# CPU_Board.net
KiCad netlist of a schematic drawn in EAGLE
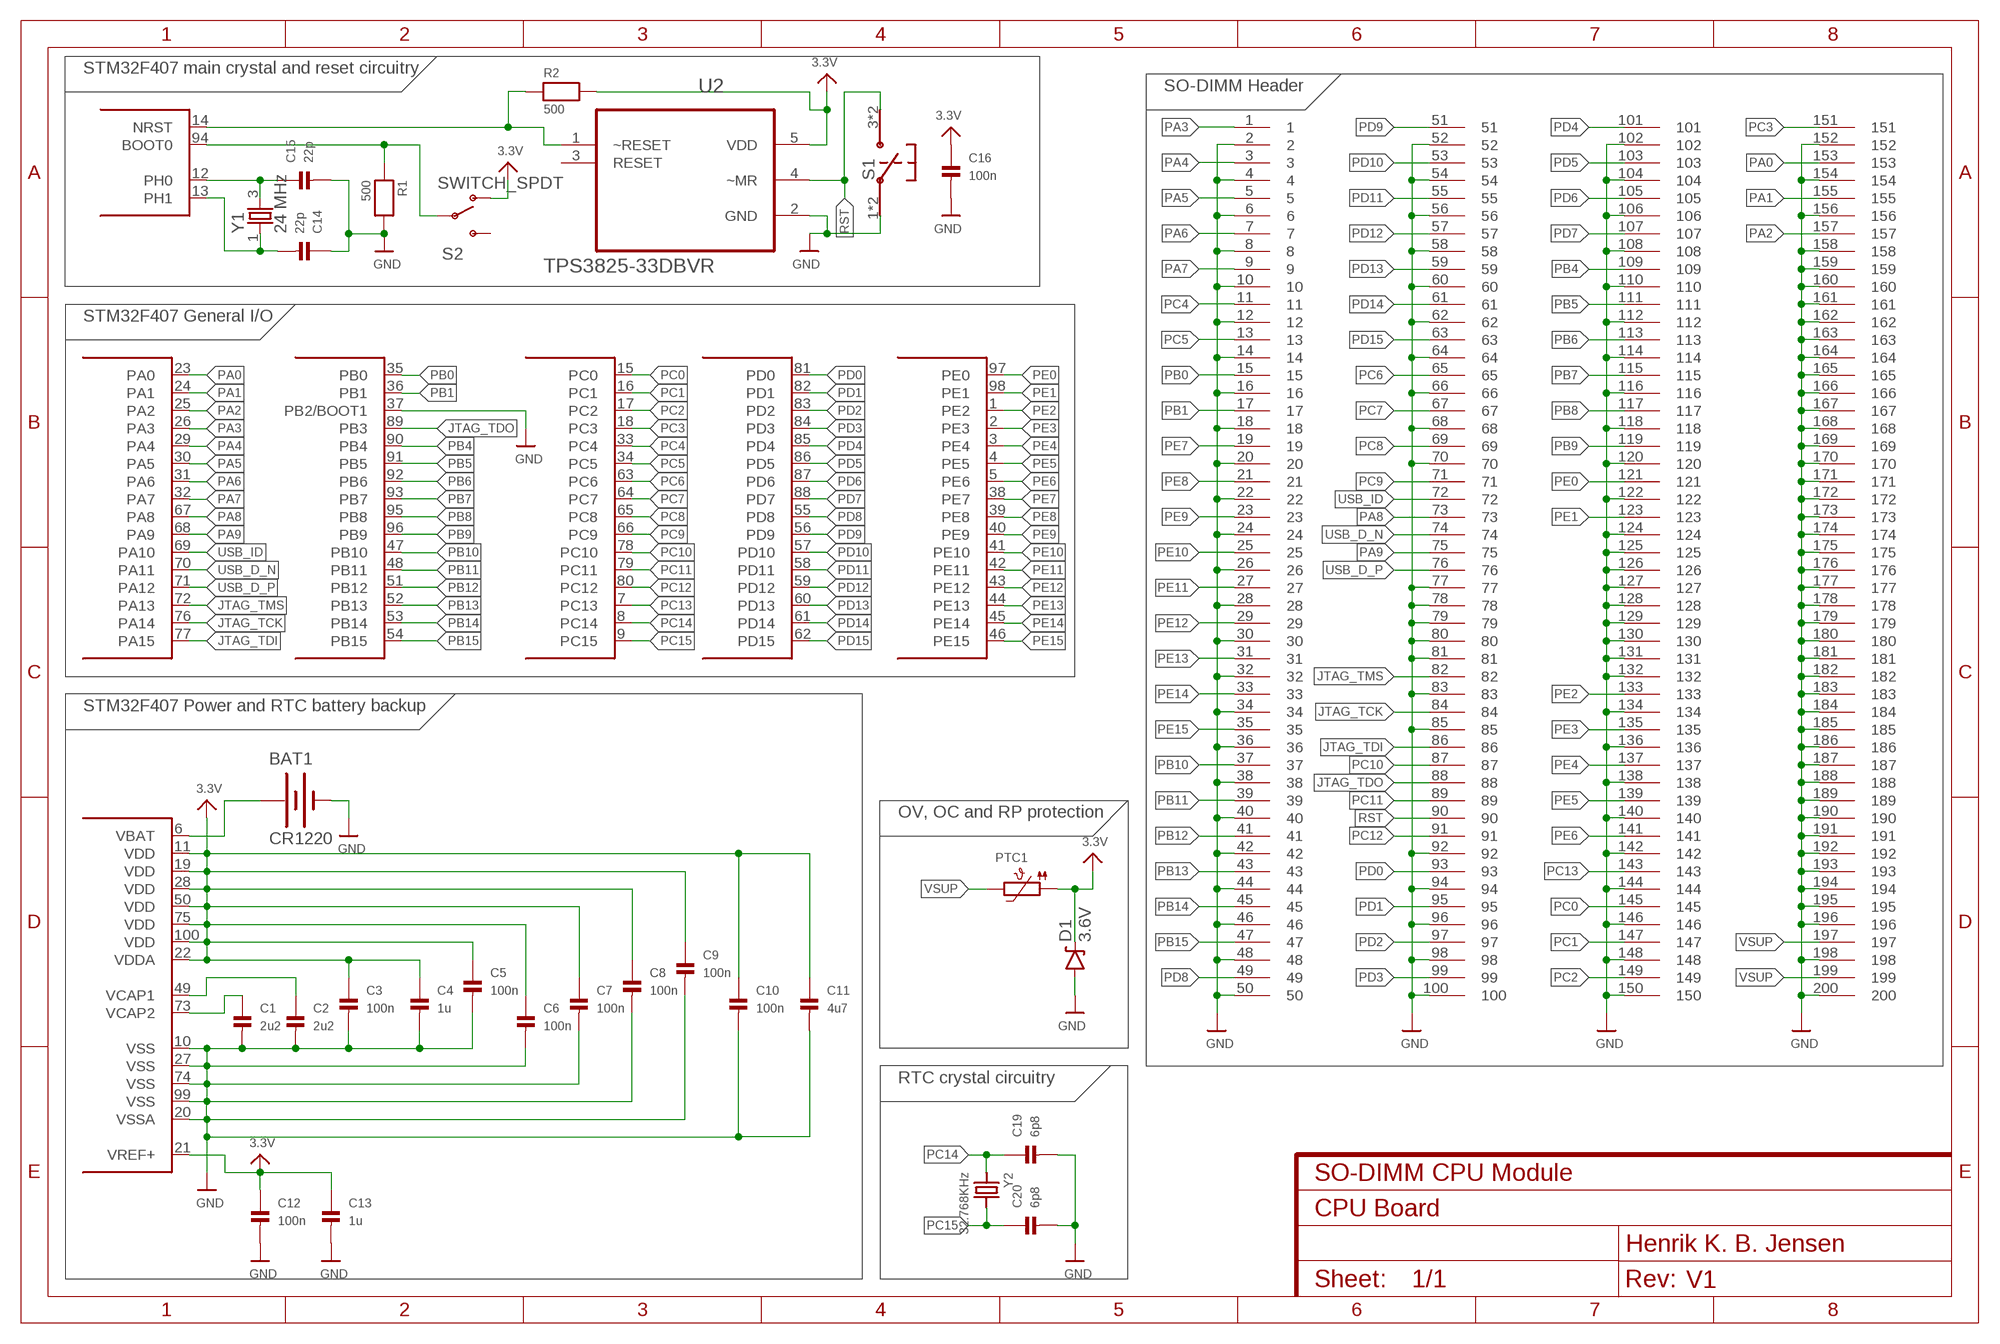
[diagram p0: schematic, sheet 1]

(export (version "E")
  (design (tool "Eeschema 10.0.6"))
  (components
    (comp (ref "BAT1")
      (value "CR1220")
      (footprint "eagle-import:BATTCON_12MM_PTH")
      (libsource (lib "eagle-import") (part "BATTERY12PTH"))
    )
    (comp (ref "C1")
      (value "2u2")
      (footprint "eagle-import:_0603")
      (libsource (lib "eagle-import") (part "CAP_CERAMIC_0603"))
    )
    (comp (ref "C2")
      (value "2u2")
      (footprint "eagle-import:_0603")
      (libsource (lib "eagle-import") (part "CAP_CERAMIC_0603"))
    )
    (comp (ref "C3")
      (value "100n")
      (footprint "eagle-import:_0603")
      (libsource (lib "eagle-import") (part "CAP_CERAMIC_0603"))
    )
    (comp (ref "C4")
      (value "1u")
      (footprint "eagle-import:_0603")
      (libsource (lib "eagle-import") (part "CAP_CERAMIC_0603"))
    )
    (comp (ref "C5")
      (value "100n")
      (footprint "eagle-import:_0603")
      (libsource (lib "eagle-import") (part "CAP_CERAMIC_0603"))
    )
    (comp (ref "C6")
      (value "100n")
      (footprint "eagle-import:_0603")
      (libsource (lib "eagle-import") (part "CAP_CERAMIC_0603"))
    )
    (comp (ref "C7")
      (value "100n")
      (footprint "eagle-import:_0603")
      (libsource (lib "eagle-import") (part "CAP_CERAMIC_0603"))
    )
    (comp (ref "C8")
      (value "100n")
      (footprint "eagle-import:_0603")
      (libsource (lib "eagle-import") (part "CAP_CERAMIC_0603"))
    )
    (comp (ref "C9")
      (value "100n")
      (footprint "eagle-import:_0603")
      (libsource (lib "eagle-import") (part "CAP_CERAMIC_0603"))
    )
    (comp (ref "C10")
      (value "100n")
      (footprint "eagle-import:_0603")
      (libsource (lib "eagle-import") (part "CAP_CERAMIC_0603"))
    )
    (comp (ref "C11")
      (value "4u7")
      (footprint "eagle-import:_0603")
      (libsource (lib "eagle-import") (part "CAP_CERAMIC_0603"))
    )
    (comp (ref "C12")
      (value "100n")
      (footprint "eagle-import:_0603")
      (libsource (lib "eagle-import") (part "CAP_CERAMIC_0603"))
    )
    (comp (ref "C13")
      (value "1u")
      (footprint "eagle-import:_0603")
      (libsource (lib "eagle-import") (part "CAP_CERAMIC_0603"))
    )
    (comp (ref "C14")
      (value "22p")
      (footprint "eagle-import:_0603")
      (libsource (lib "eagle-import") (part "CAP_CERAMIC_0603"))
    )
    (comp (ref "C15")
      (value "22p")
      (footprint "eagle-import:_0603")
      (libsource (lib "eagle-import") (part "CAP_CERAMIC_0603"))
    )
    (comp (ref "C16")
      (value "100n")
      (footprint "eagle-import:_0603")
      (libsource (lib "eagle-import") (part "CAP_CERAMIC_0603"))
    )
    (comp (ref "C19")
      (value "6p8")
      (footprint "eagle-import:_0603")
      (libsource (lib "eagle-import") (part "CAP_CERAMIC_0603"))
    )
    (comp (ref "C20")
      (value "6p8")
      (footprint "eagle-import:_0603")
      (libsource (lib "eagle-import") (part "CAP_CERAMIC_0603"))
    )
    (comp (ref "D1")
      (value "3.6V")
      (footprint "eagle-import:SOD-323")
      (libsource (lib "eagle-import") (part "DIODE-ZENER3.3V"))
    )
    (comp (ref "PTC1")
      (value "PTC1206")
      (footprint "eagle-import:1206")
      (libsource (lib "eagle-import") (part "PTC1206"))
    )
    (comp (ref "R1")
      (value "500")
      (footprint "eagle-import:_0603")
      (libsource (lib "eagle-import") (part "RESISTOR_0603"))
    )
    (comp (ref "R2")
      (value "500")
      (footprint "eagle-import:_0603")
      (libsource (lib "eagle-import") (part "RESISTOR_0603"))
    )
    (comp (ref "S1")
      (value "PTS645SM43SMTR92")
      (footprint "eagle-import:PTS645")
      (libsource (lib "eagle-import") (part "PTS645SM43SMTR92"))
    )
    (comp (ref "S2")
      (value "SWITCH_SPDT")
      (footprint "eagle-import:KPS-1290")
      (libsource (lib "eagle-import") (part "SWITCH_SPDT"))
    )
    (comp (ref "U$19")
      (value "SODIMM-2.5V-PCB")
      (footprint "eagle-import:SODIMM-2.5V-PCB")
      (libsource (lib "eagle-import") (part "SODIMM-2.5V-PCB"))
    )
    (comp (ref "U1")
      (value "STM32F4-100")
      (footprint "eagle-import:SQFP-S-14X14-100")
      (libsource (lib "eagle-import") (part "STM32F4-100"))
    )
    (comp (ref "U2")
      (value "TPS3825-33DBVR")
      (footprint "eagle-import:SOT95P280X145-5N")
      (libsource (lib "eagle-import") (part "TPS3825-33DBVR"))
    )
    (comp (ref "Y1")
      (value "24 MHz")
      (footprint "eagle-import:CRYSTAL-4PIN")
      (libsource (lib "eagle-import") (part "CRYSTAL4PIN"))
    )
    (comp (ref "Y2")
      (value "32.768KHz")
      (footprint "eagle-import:CRYSTAL_CYL_2X6MM_SMT")
      (libsource (lib "eagle-import") (part "CRYSTAL32.768"))
    )
  )
  (nets
    (net (code "1") (name "3.3V") (class "Default")
      (node (ref "C10") (pin "1") (pinfunction "P$1_1") (pintype "passive"))
      (node (ref "C11") (pin "1") (pinfunction "P$1_1") (pintype "passive"))
      (node (ref "C12") (pin "1") (pinfunction "P$1_1") (pintype "passive"))
      (node (ref "C13") (pin "1") (pinfunction "P$1_1") (pintype "passive"))
      (node (ref "C16") (pin "1") (pinfunction "P$1_1") (pintype "passive"))
      (node (ref "C3") (pin "1") (pinfunction "P$1_1") (pintype "passive"))
      (node (ref "C4") (pin "1") (pinfunction "P$1_1") (pintype "passive"))
      (node (ref "C5") (pin "1") (pinfunction "P$1_1") (pintype "passive"))
      (node (ref "C6") (pin "1") (pinfunction "P$1_1") (pintype "passive"))
      (node (ref "C7") (pin "1") (pinfunction "P$1_1") (pintype "passive"))
      (node (ref "C8") (pin "1") (pinfunction "P$1_1") (pintype "passive"))
      (node (ref "C9") (pin "1") (pinfunction "P$1_1") (pintype "passive"))
      (node (ref "D1") (pin "C") (pinfunction "C_C") (pintype "passive"))
      (node (ref "PTC1") (pin "1") (pinfunction "1_1") (pintype "passive"))
      (node (ref "R2") (pin "2") (pinfunction "2_2") (pintype "passive"))
      (node (ref "S2") (pin "O") (pinfunction "O_O") (pintype "passive"))
      (node (ref "U1") (pin "100") (pinfunction "VDD_100") (pintype "power_in"))
      (node (ref "U1") (pin "11") (pinfunction "VDD_11") (pintype "power_in"))
      (node (ref "U1") (pin "19") (pinfunction "VDD_19") (pintype "power_in"))
      (node (ref "U1") (pin "21") (pinfunction "VREF+_21") (pintype "passive"))
      (node (ref "U1") (pin "22") (pinfunction "VDDA_22") (pintype "power_in"))
      (node (ref "U1") (pin "28") (pinfunction "VDD_28") (pintype "power_in"))
      (node (ref "U1") (pin "50") (pinfunction "VDD_50") (pintype "power_in"))
      (node (ref "U1") (pin "75") (pinfunction "VDD_75") (pintype "power_in"))
      (node (ref "U2") (pin "5") (pinfunction "VDD_5") (pintype "power_in"))
    )
    (net (code "2") (name "GND") (class "Default")
      (node (ref "BAT1") (pin "GND") (pinfunction "-_GND") (pintype "power_in"))
      (node (ref "C1") (pin "2") (pinfunction "P$2_2") (pintype "passive"))
      (node (ref "C10") (pin "2") (pinfunction "P$2_2") (pintype "passive"))
      (node (ref "C11") (pin "2") (pinfunction "P$2_2") (pintype "passive"))
      (node (ref "C12") (pin "2") (pinfunction "P$2_2") (pintype "passive"))
      (node (ref "C13") (pin "2") (pinfunction "P$2_2") (pintype "passive"))
      (node (ref "C14") (pin "1") (pinfunction "P$1_1") (pintype "passive"))
      (node (ref "C15") (pin "2") (pinfunction "P$2_2") (pintype "passive"))
      (node (ref "C16") (pin "2") (pinfunction "P$2_2") (pintype "passive"))
      (node (ref "C19") (pin "2") (pinfunction "P$2_2") (pintype "passive"))
      (node (ref "C2") (pin "2") (pinfunction "P$2_2") (pintype "passive"))
      (node (ref "C20") (pin "2") (pinfunction "P$2_2") (pintype "passive"))
      (node (ref "C3") (pin "2") (pinfunction "P$2_2") (pintype "passive"))
      (node (ref "C4") (pin "2") (pinfunction "P$2_2") (pintype "passive"))
      (node (ref "C5") (pin "2") (pinfunction "P$2_2") (pintype "passive"))
      (node (ref "C6") (pin "2") (pinfunction "P$2_2") (pintype "passive"))
      (node (ref "C7") (pin "2") (pinfunction "P$2_2") (pintype "passive"))
      (node (ref "C8") (pin "2") (pinfunction "P$2_2") (pintype "passive"))
      (node (ref "C9") (pin "2") (pinfunction "P$2_2") (pintype "passive"))
      (node (ref "D1") (pin "A") (pinfunction "A_A") (pintype "passive"))
      (node (ref "R1") (pin "2") (pinfunction "2_2") (pintype "passive"))
      (node (ref "S1") (pin "1") (pinfunction "P$1_1") (pintype "passive"))
      (node (ref "S1") (pin "2") (pinfunction "P$1_2") (pintype "passive"))
      (node (ref "U$19") (pin "10") (pinfunction "10_10") (pintype "bidirectional"))
      (node (ref "U$19") (pin "100") (pinfunction "100_100") (pintype "bidirectional"))
      (node (ref "U$19") (pin "102") (pinfunction "102_102") (pintype "bidirectional"))
      (node (ref "U$19") (pin "104") (pinfunction "104_104") (pintype "bidirectional"))
      (node (ref "U$19") (pin "106") (pinfunction "106_106") (pintype "bidirectional"))
      (node (ref "U$19") (pin "108") (pinfunction "108_108") (pintype "bidirectional"))
      (node (ref "U$19") (pin "110") (pinfunction "110_110") (pintype "bidirectional"))
      (node (ref "U$19") (pin "112") (pinfunction "112_112") (pintype "bidirectional"))
      (node (ref "U$19") (pin "114") (pinfunction "114_114") (pintype "bidirectional"))
      (node (ref "U$19") (pin "116") (pinfunction "116_116") (pintype "bidirectional"))
      (node (ref "U$19") (pin "118") (pinfunction "118_118") (pintype "bidirectional"))
      (node (ref "U$19") (pin "12") (pinfunction "12_12") (pintype "bidirectional"))
      (node (ref "U$19") (pin "120") (pinfunction "120_120") (pintype "bidirectional"))
      (node (ref "U$19") (pin "122") (pinfunction "122_122") (pintype "bidirectional"))
      (node (ref "U$19") (pin "124") (pinfunction "124_124") (pintype "bidirectional"))
      (node (ref "U$19") (pin "125") (pinfunction "125_125") (pintype "bidirectional"))
      (node (ref "U$19") (pin "126") (pinfunction "126_126") (pintype "bidirectional"))
      (node (ref "U$19") (pin "127") (pinfunction "127_127") (pintype "bidirectional"))
      (node (ref "U$19") (pin "128") (pinfunction "128_128") (pintype "bidirectional"))
      (node (ref "U$19") (pin "129") (pinfunction "129_129") (pintype "bidirectional"))
      (node (ref "U$19") (pin "130") (pinfunction "130_130") (pintype "bidirectional"))
      (node (ref "U$19") (pin "131") (pinfunction "131_131") (pintype "bidirectional"))
      (node (ref "U$19") (pin "132") (pinfunction "132_132") (pintype "bidirectional"))
      (node (ref "U$19") (pin "134") (pinfunction "134_134") (pintype "bidirectional"))
      (node (ref "U$19") (pin "136") (pinfunction "136_136") (pintype "bidirectional"))
      (node (ref "U$19") (pin "138") (pinfunction "138_138") (pintype "bidirectional"))
      (node (ref "U$19") (pin "14") (pinfunction "14_14") (pintype "bidirectional"))
      (node (ref "U$19") (pin "140") (pinfunction "140_140") (pintype "bidirectional"))
      (node (ref "U$19") (pin "142") (pinfunction "142_142") (pintype "bidirectional"))
      (node (ref "U$19") (pin "144") (pinfunction "144_144") (pintype "bidirectional"))
      (node (ref "U$19") (pin "146") (pinfunction "146_146") (pintype "bidirectional"))
      (node (ref "U$19") (pin "148") (pinfunction "148_148") (pintype "bidirectional"))
      (node (ref "U$19") (pin "150") (pinfunction "150_150") (pintype "bidirectional"))
      (node (ref "U$19") (pin "152") (pinfunction "152_152") (pintype "bidirectional"))
      (node (ref "U$19") (pin "154") (pinfunction "154_154") (pintype "bidirectional"))
      (node (ref "U$19") (pin "156") (pinfunction "156_156") (pintype "bidirectional"))
      (node (ref "U$19") (pin "158") (pinfunction "158_158") (pintype "bidirectional"))
      (node (ref "U$19") (pin "159") (pinfunction "159_159") (pintype "bidirectional"))
      (node (ref "U$19") (pin "16") (pinfunction "16_16") (pintype "bidirectional"))
      (node (ref "U$19") (pin "160") (pinfunction "160_160") (pintype "bidirectional"))
      (node (ref "U$19") (pin "161") (pinfunction "161_161") (pintype "bidirectional"))
      (node (ref "U$19") (pin "162") (pinfunction "162_162") (pintype "bidirectional"))
      (node (ref "U$19") (pin "163") (pinfunction "163_163") (pintype "bidirectional"))
      (node (ref "U$19") (pin "164") (pinfunction "164_164") (pintype "bidirectional"))
      (node (ref "U$19") (pin "165") (pinfunction "165_165") (pintype "bidirectional"))
      (node (ref "U$19") (pin "166") (pinfunction "166_166") (pintype "bidirectional"))
      (node (ref "U$19") (pin "167") (pinfunction "167_167") (pintype "bidirectional"))
      (node (ref "U$19") (pin "168") (pinfunction "168_168") (pintype "bidirectional"))
      (node (ref "U$19") (pin "169") (pinfunction "169_169") (pintype "bidirectional"))
      (node (ref "U$19") (pin "170") (pinfunction "170_170") (pintype "bidirectional"))
      (node (ref "U$19") (pin "171") (pinfunction "171_171") (pintype "bidirectional"))
      (node (ref "U$19") (pin "172") (pinfunction "172_172") (pintype "bidirectional"))
      (node (ref "U$19") (pin "173") (pinfunction "173_173") (pintype "bidirectional"))
      (node (ref "U$19") (pin "174") (pinfunction "174_174") (pintype "bidirectional"))
      (node (ref "U$19") (pin "175") (pinfunction "175_175") (pintype "bidirectional"))
      (node (ref "U$19") (pin "176") (pinfunction "176_176") (pintype "bidirectional"))
      (node (ref "U$19") (pin "177") (pinfunction "177_177") (pintype "bidirectional"))
      (node (ref "U$19") (pin "178") (pinfunction "178_178") (pintype "bidirectional"))
      (node (ref "U$19") (pin "179") (pinfunction "179_179") (pintype "bidirectional"))
      (node (ref "U$19") (pin "18") (pinfunction "18_18") (pintype "bidirectional"))
      (node (ref "U$19") (pin "180") (pinfunction "180_180") (pintype "bidirectional"))
      (node (ref "U$19") (pin "181") (pinfunction "181_181") (pintype "bidirectional"))
      (node (ref "U$19") (pin "182") (pinfunction "182_182") (pintype "bidirectional"))
      (node (ref "U$19") (pin "183") (pinfunction "183_183") (pintype "bidirectional"))
      (node (ref "U$19") (pin "184") (pinfunction "184_184") (pintype "bidirectional"))
      (node (ref "U$19") (pin "185") (pinfunction "185_185") (pintype "bidirectional"))
      (node (ref "U$19") (pin "186") (pinfunction "186_186") (pintype "bidirectional"))
      (node (ref "U$19") (pin "187") (pinfunction "187_187") (pintype "bidirectional"))
      (node (ref "U$19") (pin "188") (pinfunction "188_188") (pintype "bidirectional"))
      (node (ref "U$19") (pin "189") (pinfunction "189_189") (pintype "bidirectional"))
      (node (ref "U$19") (pin "190") (pinfunction "190_190") (pintype "bidirectional"))
      (node (ref "U$19") (pin "191") (pinfunction "191_191") (pintype "bidirectional"))
      (node (ref "U$19") (pin "192") (pinfunction "192_192") (pintype "bidirectional"))
      (node (ref "U$19") (pin "193") (pinfunction "193_193") (pintype "bidirectional"))
      (node (ref "U$19") (pin "194") (pinfunction "194_194") (pintype "bidirectional"))
      (node (ref "U$19") (pin "195") (pinfunction "195_195") (pintype "bidirectional"))
      (node (ref "U$19") (pin "196") (pinfunction "196_196") (pintype "bidirectional"))
      (node (ref "U$19") (pin "198") (pinfunction "198_198") (pintype "bidirectional"))
      (node (ref "U$19") (pin "2") (pinfunction "2_2") (pintype "bidirectional"))
      (node (ref "U$19") (pin "20") (pinfunction "20_20") (pintype "bidirectional"))
      (node (ref "U$19") (pin "200") (pinfunction "200_200") (pintype "bidirectional"))
      (node (ref "U$19") (pin "22") (pinfunction "22_22") (pintype "bidirectional"))
      (node (ref "U$19") (pin "24") (pinfunction "24_24") (pintype "bidirectional"))
      (node (ref "U$19") (pin "26") (pinfunction "26_26") (pintype "bidirectional"))
      (node (ref "U$19") (pin "28") (pinfunction "28_28") (pintype "bidirectional"))
      (node (ref "U$19") (pin "30") (pinfunction "30_30") (pintype "bidirectional"))
      (node (ref "U$19") (pin "32") (pinfunction "32_32") (pintype "bidirectional"))
      (node (ref "U$19") (pin "34") (pinfunction "34_34") (pintype "bidirectional"))
      (node (ref "U$19") (pin "36") (pinfunction "36_36") (pintype "bidirectional"))
      (node (ref "U$19") (pin "38") (pinfunction "38_38") (pintype "bidirectional"))
      (node (ref "U$19") (pin "4") (pinfunction "4_4") (pintype "bidirectional"))
      (node (ref "U$19") (pin "40") (pinfunction "40_40") (pintype "bidirectional"))
      (node (ref "U$19") (pin "42") (pinfunction "42_42") (pintype "bidirectional"))
      (node (ref "U$19") (pin "44") (pinfunction "44_44") (pintype "bidirectional"))
      (node (ref "U$19") (pin "46") (pinfunction "46_46") (pintype "bidirectional"))
      (node (ref "U$19") (pin "48") (pinfunction "48_48") (pintype "bidirectional"))
      (node (ref "U$19") (pin "50") (pinfunction "50_50") (pintype "bidirectional"))
      (node (ref "U$19") (pin "52") (pinfunction "52_52") (pintype "bidirectional"))
      (node (ref "U$19") (pin "54") (pinfunction "54_54") (pintype "bidirectional"))
      (node (ref "U$19") (pin "56") (pinfunction "56_56") (pintype "bidirectional"))
      (node (ref "U$19") (pin "58") (pinfunction "58_58") (pintype "bidirectional"))
      (node (ref "U$19") (pin "6") (pinfunction "6_6") (pintype "bidirectional"))
      (node (ref "U$19") (pin "60") (pinfunction "60_60") (pintype "bidirectional"))
      (node (ref "U$19") (pin "62") (pinfunction "62_62") (pintype "bidirectional"))
      (node (ref "U$19") (pin "64") (pinfunction "64_64") (pintype "bidirectional"))
      (node (ref "U$19") (pin "66") (pinfunction "66_66") (pintype "bidirectional"))
      (node (ref "U$19") (pin "68") (pinfunction "68_68") (pintype "bidirectional"))
      (node (ref "U$19") (pin "70") (pinfunction "70_70") (pintype "bidirectional"))
      (node (ref "U$19") (pin "77") (pinfunction "77_77") (pintype "bidirectional"))
      (node (ref "U$19") (pin "78") (pinfunction "78_78") (pintype "bidirectional"))
      (node (ref "U$19") (pin "79") (pinfunction "79_79") (pintype "bidirectional"))
      (node (ref "U$19") (pin "8") (pinfunction "8_8") (pintype "bidirectional"))
      (node (ref "U$19") (pin "80") (pinfunction "80_80") (pintype "bidirectional"))
      (node (ref "U$19") (pin "81") (pinfunction "81_81") (pintype "bidirectional"))
      (node (ref "U$19") (pin "83") (pinfunction "83_83") (pintype "bidirectional"))
      (node (ref "U$19") (pin "85") (pinfunction "85_85") (pintype "bidirectional"))
      (node (ref "U$19") (pin "92") (pinfunction "92_92") (pintype "bidirectional"))
      (node (ref "U$19") (pin "94") (pinfunction "94_94") (pintype "bidirectional"))
      (node (ref "U$19") (pin "96") (pinfunction "96_96") (pintype "bidirectional"))
      (node (ref "U$19") (pin "98") (pinfunction "98_98") (pintype "bidirectional"))
      (node (ref "U1") (pin "10") (pinfunction "VSS_10") (pintype "power_in"))
      (node (ref "U1") (pin "20") (pinfunction "VSSA_20") (pintype "power_in"))
      (node (ref "U1") (pin "27") (pinfunction "VSS_27") (pintype "power_in"))
      (node (ref "U1") (pin "37") (pinfunction "PB2/BOOT1_37") (pintype "bidirectional"))
      (node (ref "U1") (pin "74") (pinfunction "VSS_74") (pintype "power_in"))
      (node (ref "U1") (pin "99") (pinfunction "VSS_99") (pintype "power_in"))
      (node (ref "U2") (pin "2") (pinfunction "GND_2") (pintype "passive"))
    )
    (net (code "3") (name "JTAG_TCK") (class "Default")
      (node (ref "U$19") (pin "84") (pinfunction "84_84") (pintype "bidirectional"))
      (node (ref "U1") (pin "76") (pinfunction "PA14_76") (pintype "bidirectional"))
    )
    (net (code "4") (name "JTAG_TDI") (class "Default")
      (node (ref "U$19") (pin "86") (pinfunction "86_86") (pintype "bidirectional"))
      (node (ref "U1") (pin "77") (pinfunction "PA15_77") (pintype "bidirectional"))
    )
    (net (code "5") (name "JTAG_TDO") (class "Default")
      (node (ref "U$19") (pin "88") (pinfunction "88_88") (pintype "bidirectional"))
      (node (ref "U1") (pin "89") (pinfunction "PB3_89") (pintype "bidirectional"))
    )
    (net (code "6") (name "JTAG_TMS") (class "Default")
      (node (ref "U$19") (pin "82") (pinfunction "82_82") (pintype "bidirectional"))
      (node (ref "U1") (pin "72") (pinfunction "PA13_72") (pintype "bidirectional"))
    )
    (net (code "7") (name "Net-(BAT1-+)") (class "Default")
      (node (ref "BAT1") (pin "VCC@1") (pinfunction "+_VCC@1") (pintype "power_in"))
      (node (ref "U1") (pin "6") (pinfunction "VBAT_6") (pintype "power_in"))
    )
    (net (code "8") (name "Net-(C1-P$1)") (class "Default")
      (node (ref "C1") (pin "1") (pinfunction "P$1_1") (pintype "passive"))
      (node (ref "U1") (pin "73") (pinfunction "VCAP2_73") (pintype "passive"))
    )
    (net (code "9") (name "Net-(C2-P$1)") (class "Default")
      (node (ref "C2") (pin "1") (pinfunction "P$1_1") (pintype "passive"))
      (node (ref "U1") (pin "49") (pinfunction "VCAP1_49") (pintype "passive"))
    )
    (net (code "10") (name "Net-(C14-P$2)") (class "Default")
      (node (ref "C14") (pin "2") (pinfunction "P$2_2") (pintype "passive"))
      (node (ref "U1") (pin "13") (pinfunction "PH1_13") (pintype "bidirectional"))
      (node (ref "Y1") (pin "1") (pinfunction "1_1") (pintype "passive"))
    )
    (net (code "11") (name "Net-(C15-P$1)") (class "Default")
      (node (ref "C15") (pin "1") (pinfunction "P$1_1") (pintype "passive"))
      (node (ref "U1") (pin "12") (pinfunction "PH0_12") (pintype "bidirectional"))
      (node (ref "Y1") (pin "3") (pinfunction "2_3") (pintype "passive"))
    )
    (net (code "12") (name "Net-(U1G-BOOT0)") (class "Default")
      (node (ref "R1") (pin "1") (pinfunction "1_1") (pintype "passive"))
      (node (ref "S2") (pin "P") (pinfunction "P_P") (pintype "passive"))
      (node (ref "U1") (pin "94") (pinfunction "BOOT0_94") (pintype "bidirectional"))
    )
    (net (code "13") (name "Net-(U1G-NRST)") (class "Default")
      (node (ref "R2") (pin "1") (pinfunction "1_1") (pintype "passive"))
      (node (ref "U1") (pin "14") (pinfunction "NRST_14") (pintype "bidirectional"))
      (node (ref "U2") (pin "1") (pinfunction "~{RESET}_1") (pintype "output"))
    )
    (net (code "14") (name "PA0") (class "Default")
      (node (ref "U$19") (pin "153") (pinfunction "153_153") (pintype "bidirectional"))
      (node (ref "U1") (pin "23") (pinfunction "PA0_23") (pintype "bidirectional"))
    )
    (net (code "15") (name "PA1") (class "Default")
      (node (ref "U$19") (pin "155") (pinfunction "155_155") (pintype "bidirectional"))
      (node (ref "U1") (pin "24") (pinfunction "PA1_24") (pintype "bidirectional"))
    )
    (net (code "16") (name "PA2") (class "Default")
      (node (ref "U$19") (pin "157") (pinfunction "157_157") (pintype "bidirectional"))
      (node (ref "U1") (pin "25") (pinfunction "PA2_25") (pintype "bidirectional"))
    )
    (net (code "17") (name "PA3") (class "Default")
      (node (ref "U$19") (pin "1") (pinfunction "1_1") (pintype "bidirectional"))
      (node (ref "U1") (pin "26") (pinfunction "PA3_26") (pintype "bidirectional"))
    )
    (net (code "18") (name "PA4") (class "Default")
      (node (ref "U$19") (pin "3") (pinfunction "3_3") (pintype "bidirectional"))
      (node (ref "U1") (pin "29") (pinfunction "PA4_29") (pintype "bidirectional"))
    )
    (net (code "19") (name "PA5") (class "Default")
      (node (ref "U$19") (pin "5") (pinfunction "5_5") (pintype "bidirectional"))
      (node (ref "U1") (pin "30") (pinfunction "PA5_30") (pintype "bidirectional"))
    )
    (net (code "20") (name "PA6") (class "Default")
      (node (ref "U$19") (pin "7") (pinfunction "7_7") (pintype "bidirectional"))
      (node (ref "U1") (pin "31") (pinfunction "PA6_31") (pintype "bidirectional"))
    )
    (net (code "21") (name "PA7") (class "Default")
      (node (ref "U$19") (pin "9") (pinfunction "9_9") (pintype "bidirectional"))
      (node (ref "U1") (pin "32") (pinfunction "PA7_32") (pintype "bidirectional"))
    )
    (net (code "22") (name "PA8") (class "Default")
      (node (ref "U$19") (pin "73") (pinfunction "73_73") (pintype "bidirectional"))
      (node (ref "U1") (pin "67") (pinfunction "PA8_67") (pintype "bidirectional"))
    )
    (net (code "23") (name "PA9") (class "Default")
      (node (ref "U$19") (pin "75") (pinfunction "75_75") (pintype "bidirectional"))
      (node (ref "U1") (pin "68") (pinfunction "PA9_68") (pintype "bidirectional"))
    )
    (net (code "24") (name "PB0") (class "Default")
      (node (ref "U$19") (pin "15") (pinfunction "15_15") (pintype "bidirectional"))
      (node (ref "U1") (pin "35") (pinfunction "PB0_35") (pintype "bidirectional"))
    )
    (net (code "25") (name "PB1") (class "Default")
      (node (ref "U$19") (pin "17") (pinfunction "17_17") (pintype "bidirectional"))
      (node (ref "U1") (pin "36") (pinfunction "PB1_36") (pintype "bidirectional"))
    )
    (net (code "26") (name "PB4") (class "Default")
      (node (ref "U$19") (pin "109") (pinfunction "109_109") (pintype "bidirectional"))
      (node (ref "U1") (pin "90") (pinfunction "PB4_90") (pintype "bidirectional"))
    )
    (net (code "27") (name "PB5") (class "Default")
      (node (ref "U$19") (pin "111") (pinfunction "111_111") (pintype "bidirectional"))
      (node (ref "U1") (pin "91") (pinfunction "PB5_91") (pintype "bidirectional"))
    )
    (net (code "28") (name "PB6") (class "Default")
      (node (ref "U$19") (pin "113") (pinfunction "113_113") (pintype "bidirectional"))
      (node (ref "U1") (pin "92") (pinfunction "PB6_92") (pintype "bidirectional"))
    )
    (net (code "29") (name "PB7") (class "Default")
      (node (ref "U$19") (pin "115") (pinfunction "115_115") (pintype "bidirectional"))
      (node (ref "U1") (pin "93") (pinfunction "PB7_93") (pintype "bidirectional"))
    )
    (net (code "30") (name "PB8") (class "Default")
      (node (ref "U$19") (pin "117") (pinfunction "117_117") (pintype "bidirectional"))
      (node (ref "U1") (pin "95") (pinfunction "PB8_95") (pintype "bidirectional"))
    )
    (net (code "31") (name "PB9") (class "Default")
      (node (ref "U$19") (pin "119") (pinfunction "119_119") (pintype "bidirectional"))
      (node (ref "U1") (pin "96") (pinfunction "PB9_96") (pintype "bidirectional"))
    )
    (net (code "32") (name "PB10") (class "Default")
      (node (ref "U$19") (pin "37") (pinfunction "37_37") (pintype "bidirectional"))
      (node (ref "U1") (pin "47") (pinfunction "PB10_47") (pintype "bidirectional"))
    )
    (net (code "33") (name "PB11") (class "Default")
      (node (ref "U$19") (pin "39") (pinfunction "39_39") (pintype "bidirectional"))
      (node (ref "U1") (pin "48") (pinfunction "PB11_48") (pintype "bidirectional"))
    )
    (net (code "34") (name "PB12") (class "Default")
      (node (ref "U$19") (pin "41") (pinfunction "41_41") (pintype "bidirectional"))
      (node (ref "U1") (pin "51") (pinfunction "PB12_51") (pintype "bidirectional"))
    )
    (net (code "35") (name "PB13") (class "Default")
      (node (ref "U$19") (pin "43") (pinfunction "43_43") (pintype "bidirectional"))
      (node (ref "U1") (pin "52") (pinfunction "PB13_52") (pintype "bidirectional"))
    )
    (net (code "36") (name "PB14") (class "Default")
      (node (ref "U$19") (pin "45") (pinfunction "45_45") (pintype "bidirectional"))
      (node (ref "U1") (pin "53") (pinfunction "PB14_53") (pintype "bidirectional"))
    )
    (net (code "37") (name "PB15") (class "Default")
      (node (ref "U$19") (pin "47") (pinfunction "47_47") (pintype "bidirectional"))
      (node (ref "U1") (pin "54") (pinfunction "PB15_54") (pintype "bidirectional"))
    )
    (net (code "38") (name "PC0") (class "Default")
      (node (ref "U$19") (pin "145") (pinfunction "145_145") (pintype "bidirectional"))
      (node (ref "U1") (pin "15") (pinfunction "PC0_15") (pintype "bidirectional"))
    )
    (net (code "39") (name "PC1") (class "Default")
      (node (ref "U$19") (pin "147") (pinfunction "147_147") (pintype "bidirectional"))
      (node (ref "U1") (pin "16") (pinfunction "PC1_16") (pintype "bidirectional"))
    )
    (net (code "40") (name "PC2") (class "Default")
      (node (ref "U$19") (pin "149") (pinfunction "149_149") (pintype "bidirectional"))
      (node (ref "U1") (pin "17") (pinfunction "PC2_17") (pintype "bidirectional"))
    )
    (net (code "41") (name "PC3") (class "Default")
      (node (ref "U$19") (pin "151") (pinfunction "151_151") (pintype "bidirectional"))
      (node (ref "U1") (pin "18") (pinfunction "PC3_18") (pintype "bidirectional"))
    )
    (net (code "42") (name "PC4") (class "Default")
      (node (ref "U$19") (pin "11") (pinfunction "11_11") (pintype "bidirectional"))
      (node (ref "U1") (pin "33") (pinfunction "PC4_33") (pintype "bidirectional"))
    )
    (net (code "43") (name "PC5") (class "Default")
      (node (ref "U$19") (pin "13") (pinfunction "13_13") (pintype "bidirectional"))
      (node (ref "U1") (pin "34") (pinfunction "PC5_34") (pintype "bidirectional"))
    )
    (net (code "44") (name "PC6") (class "Default")
      (node (ref "U$19") (pin "65") (pinfunction "65_65") (pintype "bidirectional"))
      (node (ref "U1") (pin "63") (pinfunction "PC6_63") (pintype "bidirectional"))
    )
    (net (code "45") (name "PC7") (class "Default")
      (node (ref "U$19") (pin "67") (pinfunction "67_67") (pintype "bidirectional"))
      (node (ref "U1") (pin "64") (pinfunction "PC7_64") (pintype "bidirectional"))
    )
    (net (code "46") (name "PC8") (class "Default")
      (node (ref "U$19") (pin "69") (pinfunction "69_69") (pintype "bidirectional"))
      (node (ref "U1") (pin "65") (pinfunction "PC8_65") (pintype "bidirectional"))
    )
    (net (code "47") (name "PC9") (class "Default")
      (node (ref "U$19") (pin "71") (pinfunction "71_71") (pintype "bidirectional"))
      (node (ref "U1") (pin "66") (pinfunction "PC9_66") (pintype "bidirectional"))
    )
    (net (code "48") (name "PC10") (class "Default")
      (node (ref "U$19") (pin "87") (pinfunction "87_87") (pintype "bidirectional"))
      (node (ref "U1") (pin "78") (pinfunction "PC10_78") (pintype "bidirectional"))
    )
    (net (code "49") (name "PC11") (class "Default")
      (node (ref "U$19") (pin "89") (pinfunction "89_89") (pintype "bidirectional"))
      (node (ref "U1") (pin "79") (pinfunction "PC11_79") (pintype "bidirectional"))
    )
    (net (code "50") (name "PC12") (class "Default")
      (node (ref "U$19") (pin "91") (pinfunction "91_91") (pintype "bidirectional"))
      (node (ref "U1") (pin "80") (pinfunction "PC12_80") (pintype "bidirectional"))
    )
    (net (code "51") (name "PC13") (class "Default")
      (node (ref "U$19") (pin "143") (pinfunction "143_143") (pintype "bidirectional"))
      (node (ref "U1") (pin "7") (pinfunction "PC13_7") (pintype "bidirectional"))
    )
    (net (code "52") (name "PC14") (class "Default")
      (node (ref "C19") (pin "1") (pinfunction "P$1_1") (pintype "passive"))
      (node (ref "U1") (pin "8") (pinfunction "PC14_8") (pintype "bidirectional"))
      (node (ref "Y2") (pin "1") (pinfunction "1_1") (pintype "passive"))
    )
    (net (code "53") (name "PC15") (class "Default")
      (node (ref "C20") (pin "1") (pinfunction "P$1_1") (pintype "passive"))
      (node (ref "U1") (pin "9") (pinfunction "PC15_9") (pintype "bidirectional"))
      (node (ref "Y2") (pin "2") (pinfunction "2_2") (pintype "passive"))
    )
    (net (code "54") (name "PD0") (class "Default")
      (node (ref "U$19") (pin "93") (pinfunction "93_93") (pintype "bidirectional"))
      (node (ref "U1") (pin "81") (pinfunction "PD0_81") (pintype "bidirectional"))
    )
    (net (code "55") (name "PD1") (class "Default")
      (node (ref "U$19") (pin "95") (pinfunction "95_95") (pintype "bidirectional"))
      (node (ref "U1") (pin "82") (pinfunction "PD1_82") (pintype "bidirectional"))
    )
    (net (code "56") (name "PD2") (class "Default")
      (node (ref "U$19") (pin "97") (pinfunction "97_97") (pintype "bidirectional"))
      (node (ref "U1") (pin "83") (pinfunction "PD2_83") (pintype "bidirectional"))
    )
    (net (code "57") (name "PD3") (class "Default")
      (node (ref "U$19") (pin "99") (pinfunction "99_99") (pintype "bidirectional"))
      (node (ref "U1") (pin "84") (pinfunction "PD3_84") (pintype "bidirectional"))
    )
    (net (code "58") (name "PD4") (class "Default")
      (node (ref "U$19") (pin "101") (pinfunction "101_101") (pintype "bidirectional"))
      (node (ref "U1") (pin "85") (pinfunction "PD4_85") (pintype "bidirectional"))
    )
    (net (code "59") (name "PD5") (class "Default")
      (node (ref "U$19") (pin "103") (pinfunction "103_103") (pintype "bidirectional"))
      (node (ref "U1") (pin "86") (pinfunction "PD5_86") (pintype "bidirectional"))
    )
    (net (code "60") (name "PD6") (class "Default")
      (node (ref "U$19") (pin "105") (pinfunction "105_105") (pintype "bidirectional"))
      (node (ref "U1") (pin "87") (pinfunction "PD6_87") (pintype "bidirectional"))
    )
    (net (code "61") (name "PD7") (class "Default")
      (node (ref "U$19") (pin "107") (pinfunction "107_107") (pintype "bidirectional"))
      (node (ref "U1") (pin "88") (pinfunction "PD7_88") (pintype "bidirectional"))
    )
    (net (code "62") (name "PD8") (class "Default")
      (node (ref "U$19") (pin "49") (pinfunction "49_49") (pintype "bidirectional"))
      (node (ref "U1") (pin "55") (pinfunction "PD8_55") (pintype "bidirectional"))
    )
    (net (code "63") (name "PD9") (class "Default")
      (node (ref "U$19") (pin "51") (pinfunction "51_51") (pintype "bidirectional"))
      (node (ref "U1") (pin "56") (pinfunction "PD9_56") (pintype "bidirectional"))
    )
    (net (code "64") (name "PD10") (class "Default")
      (node (ref "U$19") (pin "53") (pinfunction "53_53") (pintype "bidirectional"))
      (node (ref "U1") (pin "57") (pinfunction "PD10_57") (pintype "bidirectional"))
    )
    (net (code "65") (name "PD11") (class "Default")
      (node (ref "U$19") (pin "55") (pinfunction "55_55") (pintype "bidirectional"))
      (node (ref "U1") (pin "58") (pinfunction "PD11_58") (pintype "bidirectional"))
    )
    (net (code "66") (name "PD12") (class "Default")
      (node (ref "U$19") (pin "57") (pinfunction "57_57") (pintype "bidirectional"))
      (node (ref "U1") (pin "59") (pinfunction "PD12_59") (pintype "bidirectional"))
    )
    (net (code "67") (name "PD13") (class "Default")
      (node (ref "U$19") (pin "59") (pinfunction "59_59") (pintype "bidirectional"))
      (node (ref "U1") (pin "60") (pinfunction "PD13_60") (pintype "bidirectional"))
    )
    (net (code "68") (name "PD14") (class "Default")
      (node (ref "U$19") (pin "61") (pinfunction "61_61") (pintype "bidirectional"))
      (node (ref "U1") (pin "61") (pinfunction "PD14_61") (pintype "bidirectional"))
    )
    (net (code "69") (name "PD15") (class "Default")
      (node (ref "U$19") (pin "63") (pinfunction "63_63") (pintype "bidirectional"))
      (node (ref "U1") (pin "62") (pinfunction "PD15_62") (pintype "bidirectional"))
    )
    (net (code "70") (name "PE0") (class "Default")
      (node (ref "U$19") (pin "121") (pinfunction "121_121") (pintype "bidirectional"))
      (node (ref "U1") (pin "97") (pinfunction "PE0_97") (pintype "bidirectional"))
    )
    (net (code "71") (name "PE1") (class "Default")
      (node (ref "U$19") (pin "123") (pinfunction "123_123") (pintype "bidirectional"))
      (node (ref "U1") (pin "98") (pinfunction "PE1_98") (pintype "bidirectional"))
    )
    (net (code "72") (name "PE2") (class "Default")
      (node (ref "U$19") (pin "133") (pinfunction "133_133") (pintype "bidirectional"))
      (node (ref "U1") (pin "1") (pinfunction "PE2_1") (pintype "bidirectional"))
    )
    (net (code "73") (name "PE3") (class "Default")
      (node (ref "U$19") (pin "135") (pinfunction "135_135") (pintype "bidirectional"))
      (node (ref "U1") (pin "2") (pinfunction "PE3_2") (pintype "bidirectional"))
    )
    (net (code "74") (name "PE4") (class "Default")
      (node (ref "U$19") (pin "137") (pinfunction "137_137") (pintype "bidirectional"))
      (node (ref "U1") (pin "3") (pinfunction "PE4_3") (pintype "bidirectional"))
    )
    (net (code "75") (name "PE5") (class "Default")
      (node (ref "U$19") (pin "139") (pinfunction "139_139") (pintype "bidirectional"))
      (node (ref "U1") (pin "4") (pinfunction "PE5_4") (pintype "bidirectional"))
    )
    (net (code "76") (name "PE6") (class "Default")
      (node (ref "U$19") (pin "141") (pinfunction "141_141") (pintype "bidirectional"))
      (node (ref "U1") (pin "5") (pinfunction "PE6_5") (pintype "bidirectional"))
    )
    (net (code "77") (name "PE7") (class "Default")
      (node (ref "U$19") (pin "19") (pinfunction "19_19") (pintype "bidirectional"))
      (node (ref "U1") (pin "38") (pinfunction "PE7_38") (pintype "bidirectional"))
    )
    (net (code "78") (name "PE8") (class "Default")
      (node (ref "U$19") (pin "21") (pinfunction "21_21") (pintype "bidirectional"))
      (node (ref "U1") (pin "39") (pinfunction "PE8_39") (pintype "bidirectional"))
    )
    (net (code "79") (name "PE9") (class "Default")
      (node (ref "U$19") (pin "23") (pinfunction "23_23") (pintype "bidirectional"))
      (node (ref "U1") (pin "40") (pinfunction "PE9_40") (pintype "bidirectional"))
    )
    (net (code "80") (name "PE10") (class "Default")
      (node (ref "U$19") (pin "25") (pinfunction "25_25") (pintype "bidirectional"))
      (node (ref "U1") (pin "41") (pinfunction "PE10_41") (pintype "bidirectional"))
    )
    (net (code "81") (name "PE11") (class "Default")
      (node (ref "U$19") (pin "27") (pinfunction "27_27") (pintype "bidirectional"))
      (node (ref "U1") (pin "42") (pinfunction "PE11_42") (pintype "bidirectional"))
    )
    (net (code "82") (name "PE12") (class "Default")
      (node (ref "U$19") (pin "29") (pinfunction "29_29") (pintype "bidirectional"))
      (node (ref "U1") (pin "43") (pinfunction "PE12_43") (pintype "bidirectional"))
    )
    (net (code "83") (name "PE13") (class "Default")
      (node (ref "U$19") (pin "31") (pinfunction "31_31") (pintype "bidirectional"))
      (node (ref "U1") (pin "44") (pinfunction "PE13_44") (pintype "bidirectional"))
    )
    (net (code "84") (name "PE14") (class "Default")
      (node (ref "U$19") (pin "33") (pinfunction "33_33") (pintype "bidirectional"))
      (node (ref "U1") (pin "45") (pinfunction "PE14_45") (pintype "bidirectional"))
    )
    (net (code "85") (name "PE15") (class "Default")
      (node (ref "U$19") (pin "35") (pinfunction "35_35") (pintype "bidirectional"))
      (node (ref "U1") (pin "46") (pinfunction "PE15_46") (pintype "bidirectional"))
    )
    (net (code "86") (name "RST") (class "Default")
      (node (ref "S1") (pin "3") (pinfunction "P$2_3") (pintype "passive"))
      (node (ref "S1") (pin "4") (pinfunction "P$2_4") (pintype "passive"))
      (node (ref "U$19") (pin "90") (pinfunction "90_90") (pintype "bidirectional"))
      (node (ref "U2") (pin "4") (pinfunction "~{MR}_4") (pintype "input"))
    )
    (net (code "87") (name "USB_D_N") (class "Default")
      (node (ref "U$19") (pin "74") (pinfunction "74_74") (pintype "bidirectional"))
      (node (ref "U1") (pin "70") (pinfunction "PA11_70") (pintype "bidirectional"))
    )
    (net (code "88") (name "USB_D_P") (class "Default")
      (node (ref "U$19") (pin "76") (pinfunction "76_76") (pintype "bidirectional"))
      (node (ref "U1") (pin "71") (pinfunction "PA12_71") (pintype "bidirectional"))
    )
    (net (code "89") (name "USB_ID") (class "Default")
      (node (ref "U$19") (pin "72") (pinfunction "72_72") (pintype "bidirectional"))
      (node (ref "U1") (pin "69") (pinfunction "PA10_69") (pintype "bidirectional"))
    )
    (net (code "90") (name "VSUP") (class "Default")
      (node (ref "PTC1") (pin "2") (pinfunction "2_2") (pintype "passive"))
      (node (ref "U$19") (pin "197") (pinfunction "197_197") (pintype "bidirectional"))
      (node (ref "U$19") (pin "199") (pinfunction "199_199") (pintype "bidirectional"))
    )
    (net (code "91") (name "unconnected-(S2-PadS)") (class "Default")
      (node (ref "S2") (pin "S") (pinfunction "S_S") (pintype "passive"))
    )
    (net (code "92") (name "unconnected-(U2-RESET-Pad3)") (class "Default")
      (node (ref "U2") (pin "3") (pinfunction "RESET_3") (pintype "output"))
    )
  )
)
